# main_board.net
KiCad netlist of a schematic drawn in EAGLE
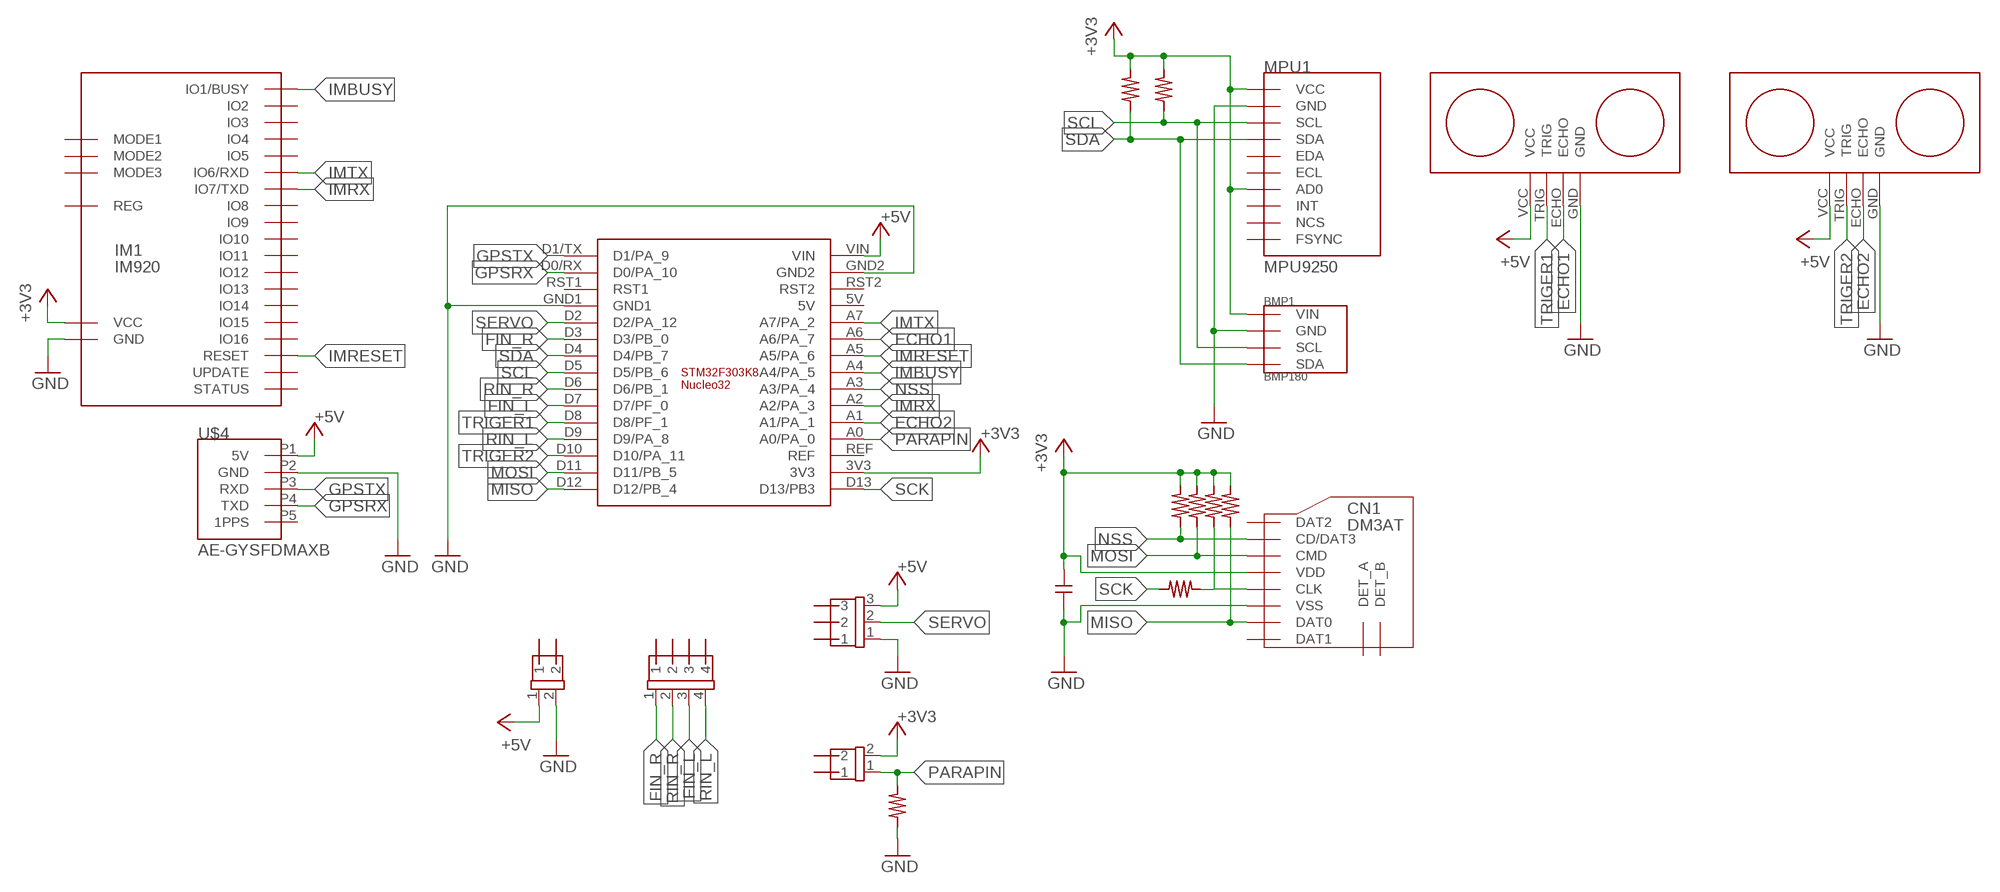
[diagram p0: schematic, sheet 1]

(export (version "E")
  (design (tool "Eeschema 10.0.6"))
  (components
    (comp (ref "BMP1")
      (value "BMP180")
      (footprint "eagle-import:GY-68")
      (libsource (lib "eagle-import") (part "BMP180"))
    )
    (comp (ref "C4")
      (value "CAPACITOR-CERAMICC_1")
      (footprint "eagle-import:CAPACITOR-CERAMICC_1")
      (libsource (lib "eagle-import") (part "CAPACITOR-CERAMICC_1"))
    )
    (comp (ref "CN1")
      (value "DM3AT")
      (footprint "eagle-import:DM3AT")
      (libsource (lib "eagle-import") (part "DM3AT"))
    )
    (comp (ref "CONN1")
      (value "2PIN")
      (footprint "eagle-import:2PIN")
      (libsource (lib "eagle-import") (part "2PIN"))
    )
    (comp (ref "CONN2")
      (value "2PIN")
      (footprint "eagle-import:2PIN")
      (libsource (lib "eagle-import") (part "2PIN"))
    )
    (comp (ref "CONN3")
      (value "4PIN")
      (footprint "eagle-import:4PIN")
      (libsource (lib "eagle-import") (part "4PIN"))
    )
    (comp (ref "CONN4")
      (value "3PIN")
      (footprint "eagle-import:3PIN")
      (libsource (lib "eagle-import") (part "3PIN"))
    )
    (comp (ref "CP1")
      (value "STM32F303K8-NUCLEO32")
      (footprint "eagle-import:STM32-NUCLEO32")
      (libsource (lib "eagle-import") (part "STM32F303K8-NUCLEO32"))
    )
    (comp (ref "EC1")
      (value "ECHO")
      (footprint "eagle-import:ECHO")
      (libsource (lib "eagle-import") (part "ECHO"))
    )
    (comp (ref "EC2")
      (value "ECHO")
      (footprint "eagle-import:ECHO")
      (libsource (lib "eagle-import") (part "ECHO"))
    )
    (comp (ref "IM1")
      (value "IM920")
      (footprint "eagle-import:IM920")
      (libsource (lib "eagle-import") (part "IM920"))
    )
    (comp (ref "MPU1")
      (value "MPU9250")
      (footprint "eagle-import:GY-9250")
      (libsource (lib "eagle-import") (part "MPU9250"))
    )
    (comp (ref "R2")
      (value "RESISTER")
      (footprint "eagle-import:REGISTER")
      (libsource (lib "eagle-import") (part "RESISTER"))
    )
    (comp (ref "R4")
      (value "RESISTER")
      (footprint "eagle-import:REGISTER")
      (libsource (lib "eagle-import") (part "RESISTER"))
    )
    (comp (ref "R5")
      (value "RESISTER")
      (footprint "eagle-import:REGISTER")
      (libsource (lib "eagle-import") (part "RESISTER"))
    )
    (comp (ref "R6")
      (value "RESISTER")
      (footprint "eagle-import:REGISTER")
      (libsource (lib "eagle-import") (part "RESISTER"))
    )
    (comp (ref "R7")
      (value "RESISTER")
      (footprint "eagle-import:REGISTER")
      (libsource (lib "eagle-import") (part "RESISTER"))
    )
    (comp (ref "R8")
      (value "RESISTER")
      (footprint "eagle-import:REGISTER")
      (libsource (lib "eagle-import") (part "RESISTER"))
    )
    (comp (ref "R9")
      (value "RESISTER")
      (footprint "eagle-import:REGISTER")
      (libsource (lib "eagle-import") (part "RESISTER"))
    )
    (comp (ref "R10")
      (value "RESISTER")
      (footprint "eagle-import:REGISTER")
      (libsource (lib "eagle-import") (part "RESISTER"))
    )
    (comp (ref "U$4")
      (value "AE-GYSFDMAXB")
      (footprint "eagle-import:AE-GYSFDMAXB")
      (libsource (lib "eagle-import") (part "AE-GYSFDMAXB"))
    )
  )
  (nets
    (net (code "1") (name "+3V3") (class "Default")
      (node (ref "BMP1") (pin "P1") (pinfunction "VIN_P1") (pintype "bidirectional"))
      (node (ref "C4") (pin "2") (pinfunction "2_2") (pintype "bidirectional"))
      (node (ref "CN1") (pin "VDD") (pinfunction "VDD_VDD") (pintype "bidirectional"))
      (node (ref "CONN1") (pin "2") (pinfunction "2_2") (pintype "bidirectional"))
      (node (ref "CP1") (pin "3V3") (pinfunction "3V3_3V3") (pintype "bidirectional"))
      (node (ref "IM1") (pin "IO23") (pinfunction "VCC_IO23") (pintype "bidirectional"))
      (node (ref "MPU1") (pin "P1") (pinfunction "VCC_P1") (pintype "bidirectional"))
      (node (ref "MPU1") (pin "P7") (pinfunction "AD0_P7") (pintype "bidirectional"))
      (node (ref "R4") (pin "B") (pinfunction "B_B") (pintype "bidirectional"))
      (node (ref "R5") (pin "B") (pinfunction "B_B") (pintype "bidirectional"))
      (node (ref "R6") (pin "B") (pinfunction "B_B") (pintype "bidirectional"))
      (node (ref "R7") (pin "B") (pinfunction "B_B") (pintype "bidirectional"))
      (node (ref "R8") (pin "B") (pinfunction "B_B") (pintype "bidirectional"))
      (node (ref "R9") (pin "B") (pinfunction "B_B") (pintype "bidirectional"))
    )
    (net (code "2") (name "+5V") (class "Default")
      (node (ref "CONN2") (pin "1") (pinfunction "1_1") (pintype "bidirectional"))
      (node (ref "CONN4") (pin "3") (pinfunction "3_3") (pintype "bidirectional"))
      (node (ref "CP1") (pin "VIN") (pinfunction "VIN_VIN") (pintype "bidirectional"))
      (node (ref "EC1") (pin "VCC") (pinfunction "VCC_VCC") (pintype "bidirectional"))
      (node (ref "EC2") (pin "VCC") (pinfunction "VCC_VCC") (pintype "bidirectional"))
      (node (ref "U$4") (pin "P1") (pinfunction "5V_P1") (pintype "bidirectional"))
    )
    (net (code "3") (name "ECHO1") (class "Default")
      (node (ref "CP1") (pin "A6") (pinfunction "A6/PA_7_A6") (pintype "bidirectional"))
      (node (ref "EC1") (pin "ECHO") (pinfunction "ECHO_ECHO") (pintype "bidirectional"))
    )
    (net (code "4") (name "ECHO2") (class "Default")
      (node (ref "CP1") (pin "A1") (pinfunction "A1/PA_1_A1") (pintype "bidirectional"))
      (node (ref "EC2") (pin "ECHO") (pinfunction "ECHO_ECHO") (pintype "bidirectional"))
    )
    (net (code "5") (name "FIN_L") (class "Default")
      (node (ref "CONN3") (pin "3") (pinfunction "3_3") (pintype "bidirectional"))
      (node (ref "CP1") (pin "D7") (pinfunction "D7/PF_0_D7") (pintype "bidirectional"))
    )
    (net (code "6") (name "FIN_R") (class "Default")
      (node (ref "CONN3") (pin "1") (pinfunction "1_1") (pintype "bidirectional"))
      (node (ref "CP1") (pin "D3") (pinfunction "D3/PB_0_D3") (pintype "bidirectional"))
    )
    (net (code "7") (name "GND") (class "Default")
      (node (ref "BMP1") (pin "P2") (pinfunction "GND_P2") (pintype "bidirectional"))
      (node (ref "C4") (pin "1") (pinfunction "1_1") (pintype "bidirectional"))
      (node (ref "CN1") (pin "VSS") (pinfunction "VSS_VSS") (pintype "bidirectional"))
      (node (ref "CONN2") (pin "2") (pinfunction "2_2") (pintype "bidirectional"))
      (node (ref "CONN4") (pin "1") (pinfunction "1_1") (pintype "bidirectional"))
      (node (ref "CP1") (pin "GND1") (pinfunction "GND1_GND1") (pintype "bidirectional"))
      (node (ref "CP1") (pin "GND2") (pinfunction "GND2_GND2") (pintype "bidirectional"))
      (node (ref "EC1") (pin "GND") (pinfunction "GND_GND") (pintype "bidirectional"))
      (node (ref "EC2") (pin "GND") (pinfunction "GND_GND") (pintype "bidirectional"))
      (node (ref "IM1") (pin "IO24") (pinfunction "GND_IO24") (pintype "bidirectional"))
      (node (ref "MPU1") (pin "P2") (pinfunction "GND_P2") (pintype "bidirectional"))
      (node (ref "R2") (pin "A") (pinfunction "A_A") (pintype "bidirectional"))
      (node (ref "U$4") (pin "P2") (pinfunction "GND_P2") (pintype "bidirectional"))
    )
    (net (code "8") (name "GPSRX") (class "Default")
      (node (ref "CP1") (pin "D0/RX") (pinfunction "D0/PA_10_D0/RX") (pintype "bidirectional"))
      (node (ref "U$4") (pin "P4") (pinfunction "TXD_P4") (pintype "bidirectional"))
    )
    (net (code "9") (name "GPSTX") (class "Default")
      (node (ref "CP1") (pin "D1/TX") (pinfunction "D1/PA_9_D1/TX") (pintype "bidirectional"))
      (node (ref "U$4") (pin "P3") (pinfunction "RXD_P3") (pintype "bidirectional"))
    )
    (net (code "10") (name "IMBUSY") (class "Default")
      (node (ref "CP1") (pin "A4") (pinfunction "A4/PA_5_A4") (pintype "bidirectional"))
      (node (ref "IM1") (pin "IO1") (pinfunction "IO1/BUSY_IO1") (pintype "bidirectional"))
    )
    (net (code "11") (name "IMRESET") (class "Default")
      (node (ref "CP1") (pin "A5") (pinfunction "A5/PA_6_A5") (pintype "bidirectional"))
      (node (ref "IM1") (pin "IO25") (pinfunction "RESET_IO25") (pintype "bidirectional"))
    )
    (net (code "12") (name "IMRX") (class "Default")
      (node (ref "CP1") (pin "A2") (pinfunction "A2/PA_3_A2") (pintype "bidirectional"))
      (node (ref "IM1") (pin "IO7") (pinfunction "IO7/TXD_IO7") (pintype "bidirectional"))
    )
    (net (code "13") (name "IMTX") (class "Default")
      (node (ref "CP1") (pin "A7") (pinfunction "A7/PA_2_A7") (pintype "bidirectional"))
      (node (ref "IM1") (pin "IO6") (pinfunction "IO6/RXD_IO6") (pintype "bidirectional"))
    )
    (net (code "14") (name "MISO") (class "Default")
      (node (ref "CN1") (pin "DAT0") (pinfunction "DAT0_DAT0") (pintype "bidirectional"))
      (node (ref "CP1") (pin "D12") (pinfunction "D12/PB_4_D12") (pintype "bidirectional"))
      (node (ref "R6") (pin "A") (pinfunction "A_A") (pintype "bidirectional"))
    )
    (net (code "15") (name "MOSI") (class "Default")
      (node (ref "CN1") (pin "CMD") (pinfunction "CMD_CMD") (pintype "bidirectional"))
      (node (ref "CP1") (pin "D11") (pinfunction "D11/PB_5_D11") (pintype "bidirectional"))
      (node (ref "R8") (pin "A") (pinfunction "A_A") (pintype "bidirectional"))
    )
    (net (code "16") (name "NSS") (class "Default")
      (node (ref "CN1") (pin "CD/DAT3") (pinfunction "CD/DAT3_CD/DAT3") (pintype "bidirectional"))
      (node (ref "CP1") (pin "A3") (pinfunction "A3/PA_4_A3") (pintype "bidirectional"))
      (node (ref "R9") (pin "A") (pinfunction "A_A") (pintype "bidirectional"))
    )
    (net (code "17") (name "Net-(CN1-PadCLK)") (class "Default")
      (node (ref "CN1") (pin "CLK") (pinfunction "CLK_CLK") (pintype "bidirectional"))
      (node (ref "R10") (pin "B") (pinfunction "B_B") (pintype "bidirectional"))
      (node (ref "R7") (pin "A") (pinfunction "A_A") (pintype "bidirectional"))
    )
    (net (code "18") (name "PARAPIN") (class "Default")
      (node (ref "CONN1") (pin "1") (pinfunction "1_1") (pintype "bidirectional"))
      (node (ref "CP1") (pin "A0") (pinfunction "A0/PA_0_A0") (pintype "bidirectional"))
      (node (ref "R2") (pin "B") (pinfunction "B_B") (pintype "bidirectional"))
    )
    (net (code "19") (name "RIN_L") (class "Default")
      (node (ref "CONN3") (pin "4") (pinfunction "4_4") (pintype "bidirectional"))
      (node (ref "CP1") (pin "D9") (pinfunction "D9/PA_8_D9") (pintype "bidirectional"))
    )
    (net (code "20") (name "RIN_R") (class "Default")
      (node (ref "CONN3") (pin "2") (pinfunction "2_2") (pintype "bidirectional"))
      (node (ref "CP1") (pin "D6") (pinfunction "D6/PB_1_D6") (pintype "bidirectional"))
    )
    (net (code "21") (name "SCK") (class "Default")
      (node (ref "CP1") (pin "D13") (pinfunction "D13/PB3_D13") (pintype "bidirectional"))
      (node (ref "R10") (pin "A") (pinfunction "A_A") (pintype "bidirectional"))
    )
    (net (code "22") (name "SCL") (class "Default")
      (node (ref "BMP1") (pin "P3") (pinfunction "SCL_P3") (pintype "bidirectional"))
      (node (ref "CP1") (pin "D5") (pinfunction "D5/PB_6_D5") (pintype "bidirectional"))
      (node (ref "MPU1") (pin "P3") (pinfunction "SCL_P3") (pintype "bidirectional"))
      (node (ref "R4") (pin "A") (pinfunction "A_A") (pintype "bidirectional"))
    )
    (net (code "23") (name "SDA") (class "Default")
      (node (ref "BMP1") (pin "P4") (pinfunction "SDA_P4") (pintype "bidirectional"))
      (node (ref "CP1") (pin "D4") (pinfunction "D4/PB_7_D4") (pintype "bidirectional"))
      (node (ref "MPU1") (pin "P4") (pinfunction "SDA_P4") (pintype "bidirectional"))
      (node (ref "R5") (pin "A") (pinfunction "A_A") (pintype "bidirectional"))
    )
    (net (code "24") (name "SERVO") (class "Default")
      (node (ref "CONN4") (pin "2") (pinfunction "2_2") (pintype "bidirectional"))
      (node (ref "CP1") (pin "D2") (pinfunction "D2/PA_12_D2") (pintype "bidirectional"))
    )
    (net (code "25") (name "TRIGER1") (class "Default")
      (node (ref "CP1") (pin "D8") (pinfunction "D8/PF_1_D8") (pintype "bidirectional"))
      (node (ref "EC1") (pin "TRIG") (pinfunction "TRIG_TRIG") (pintype "bidirectional"))
    )
    (net (code "26") (name "TRIGER2") (class "Default")
      (node (ref "CP1") (pin "D10") (pinfunction "D10/PA_11_D10") (pintype "bidirectional"))
      (node (ref "EC2") (pin "TRIG") (pinfunction "TRIG_TRIG") (pintype "bidirectional"))
    )
    (net (code "27") (name "unconnected-(CN1-PadDAT1)") (class "Default")
      (node (ref "CN1") (pin "DAT1") (pinfunction "DAT1_DAT1") (pintype "bidirectional"))
    )
    (net (code "28") (name "unconnected-(CN1-PadDAT2)") (class "Default")
      (node (ref "CN1") (pin "DAT2") (pinfunction "DAT2_DAT2") (pintype "bidirectional"))
    )
    (net (code "29") (name "unconnected-(CN1-PadDET_A)") (class "Default")
      (node (ref "CN1") (pin "DET_A") (pinfunction "DET_A_DET_A") (pintype "bidirectional"))
    )
    (net (code "30") (name "unconnected-(CN1-PadDET_B)") (class "Default")
      (node (ref "CN1") (pin "DET_B") (pinfunction "DET_B_DET_B") (pintype "bidirectional"))
    )
    (net (code "31") (name "unconnected-(CP1-Pad5V)") (class "Default")
      (node (ref "CP1") (pin "5V") (pinfunction "5V_5V") (pintype "bidirectional"))
    )
    (net (code "32") (name "unconnected-(CP1-PadREF)") (class "Default")
      (node (ref "CP1") (pin "REF") (pinfunction "REF_REF") (pintype "bidirectional"))
    )
    (net (code "33") (name "unconnected-(CP1-PadRST1)") (class "Default")
      (node (ref "CP1") (pin "RST1") (pinfunction "RST1_RST1") (pintype "bidirectional"))
    )
    (net (code "34") (name "unconnected-(CP1-PadRST2)") (class "Default")
      (node (ref "CP1") (pin "RST2") (pinfunction "RST2_RST2") (pintype "bidirectional"))
    )
    (net (code "35") (name "unconnected-(IM1-MODE1-PadIO17)") (class "Default")
      (node (ref "IM1") (pin "IO17") (pinfunction "MODE1_IO17") (pintype "bidirectional"))
    )
    (net (code "36") (name "unconnected-(IM1-MODE2-PadIO18)") (class "Default")
      (node (ref "IM1") (pin "IO18") (pinfunction "MODE2_IO18") (pintype "bidirectional"))
    )
    (net (code "37") (name "unconnected-(IM1-MODE3-PadIO19)") (class "Default")
      (node (ref "IM1") (pin "IO19") (pinfunction "MODE3_IO19") (pintype "bidirectional"))
    )
    (net (code "38") (name "unconnected-(IM1-PadIO2)") (class "Default")
      (node (ref "IM1") (pin "IO2") (pinfunction "IO2_IO2") (pintype "bidirectional"))
    )
    (net (code "39") (name "unconnected-(IM1-PadIO3)") (class "Default")
      (node (ref "IM1") (pin "IO3") (pinfunction "IO3_IO3") (pintype "bidirectional"))
    )
    (net (code "40") (name "unconnected-(IM1-PadIO4)") (class "Default")
      (node (ref "IM1") (pin "IO4") (pinfunction "IO4_IO4") (pintype "bidirectional"))
    )
    (net (code "41") (name "unconnected-(IM1-PadIO5)") (class "Default")
      (node (ref "IM1") (pin "IO5") (pinfunction "IO5_IO5") (pintype "bidirectional"))
    )
    (net (code "42") (name "unconnected-(IM1-PadIO8)") (class "Default")
      (node (ref "IM1") (pin "IO8") (pinfunction "IO8_IO8") (pintype "bidirectional"))
    )
    (net (code "43") (name "unconnected-(IM1-PadIO9)") (class "Default")
      (node (ref "IM1") (pin "IO9") (pinfunction "IO9_IO9") (pintype "bidirectional"))
    )
    (net (code "44") (name "unconnected-(IM1-PadIO10)") (class "Default")
      (node (ref "IM1") (pin "IO10") (pinfunction "IO10_IO10") (pintype "bidirectional"))
    )
    (net (code "45") (name "unconnected-(IM1-PadIO11)") (class "Default")
      (node (ref "IM1") (pin "IO11") (pinfunction "IO11_IO11") (pintype "bidirectional"))
    )
    (net (code "46") (name "unconnected-(IM1-PadIO12)") (class "Default")
      (node (ref "IM1") (pin "IO12") (pinfunction "IO12_IO12") (pintype "bidirectional"))
    )
    (net (code "47") (name "unconnected-(IM1-PadIO13)") (class "Default")
      (node (ref "IM1") (pin "IO13") (pinfunction "IO13_IO13") (pintype "bidirectional"))
    )
    (net (code "48") (name "unconnected-(IM1-PadIO14)") (class "Default")
      (node (ref "IM1") (pin "IO14") (pinfunction "IO14_IO14") (pintype "bidirectional"))
    )
    (net (code "49") (name "unconnected-(IM1-PadIO15)") (class "Default")
      (node (ref "IM1") (pin "IO15") (pinfunction "IO15_IO15") (pintype "bidirectional"))
    )
    (net (code "50") (name "unconnected-(IM1-PadIO16)") (class "Default")
      (node (ref "IM1") (pin "IO16") (pinfunction "IO16_IO16") (pintype "bidirectional"))
    )
    (net (code "51") (name "unconnected-(IM1-REG-PadIO22)") (class "Default")
      (node (ref "IM1") (pin "IO22") (pinfunction "REG_IO22") (pintype "bidirectional"))
    )
    (net (code "52") (name "unconnected-(IM1-STATUS-PadIO21)") (class "Default")
      (node (ref "IM1") (pin "IO21") (pinfunction "STATUS_IO21") (pintype "bidirectional"))
    )
    (net (code "53") (name "unconnected-(IM1-UPDATE-PadIO20)") (class "Default")
      (node (ref "IM1") (pin "IO20") (pinfunction "UPDATE_IO20") (pintype "bidirectional"))
    )
    (net (code "54") (name "unconnected-(MPU1-ECL-PadP6)") (class "Default")
      (node (ref "MPU1") (pin "P6") (pinfunction "ECL_P6") (pintype "bidirectional"))
    )
    (net (code "55") (name "unconnected-(MPU1-EDA-PadP5)") (class "Default")
      (node (ref "MPU1") (pin "P5") (pinfunction "EDA_P5") (pintype "bidirectional"))
    )
    (net (code "56") (name "unconnected-(MPU1-FSYNC-PadP10)") (class "Default")
      (node (ref "MPU1") (pin "P10") (pinfunction "FSYNC_P10") (pintype "bidirectional"))
    )
    (net (code "57") (name "unconnected-(MPU1-INT-PadP8)") (class "Default")
      (node (ref "MPU1") (pin "P8") (pinfunction "INT_P8") (pintype "bidirectional"))
    )
    (net (code "58") (name "unconnected-(MPU1-NCS-PadP9)") (class "Default")
      (node (ref "MPU1") (pin "P9") (pinfunction "NCS_P9") (pintype "bidirectional"))
    )
    (net (code "59") (name "unconnected-(U$4-1PPS-PadP5)") (class "Default")
      (node (ref "U$4") (pin "P5") (pinfunction "1PPS_P5") (pintype "bidirectional"))
    )
  )
)
